# CC_SoC_Debugger_Ver1_02.net
KiCad netlist of a schematic drawn in Altium Designer
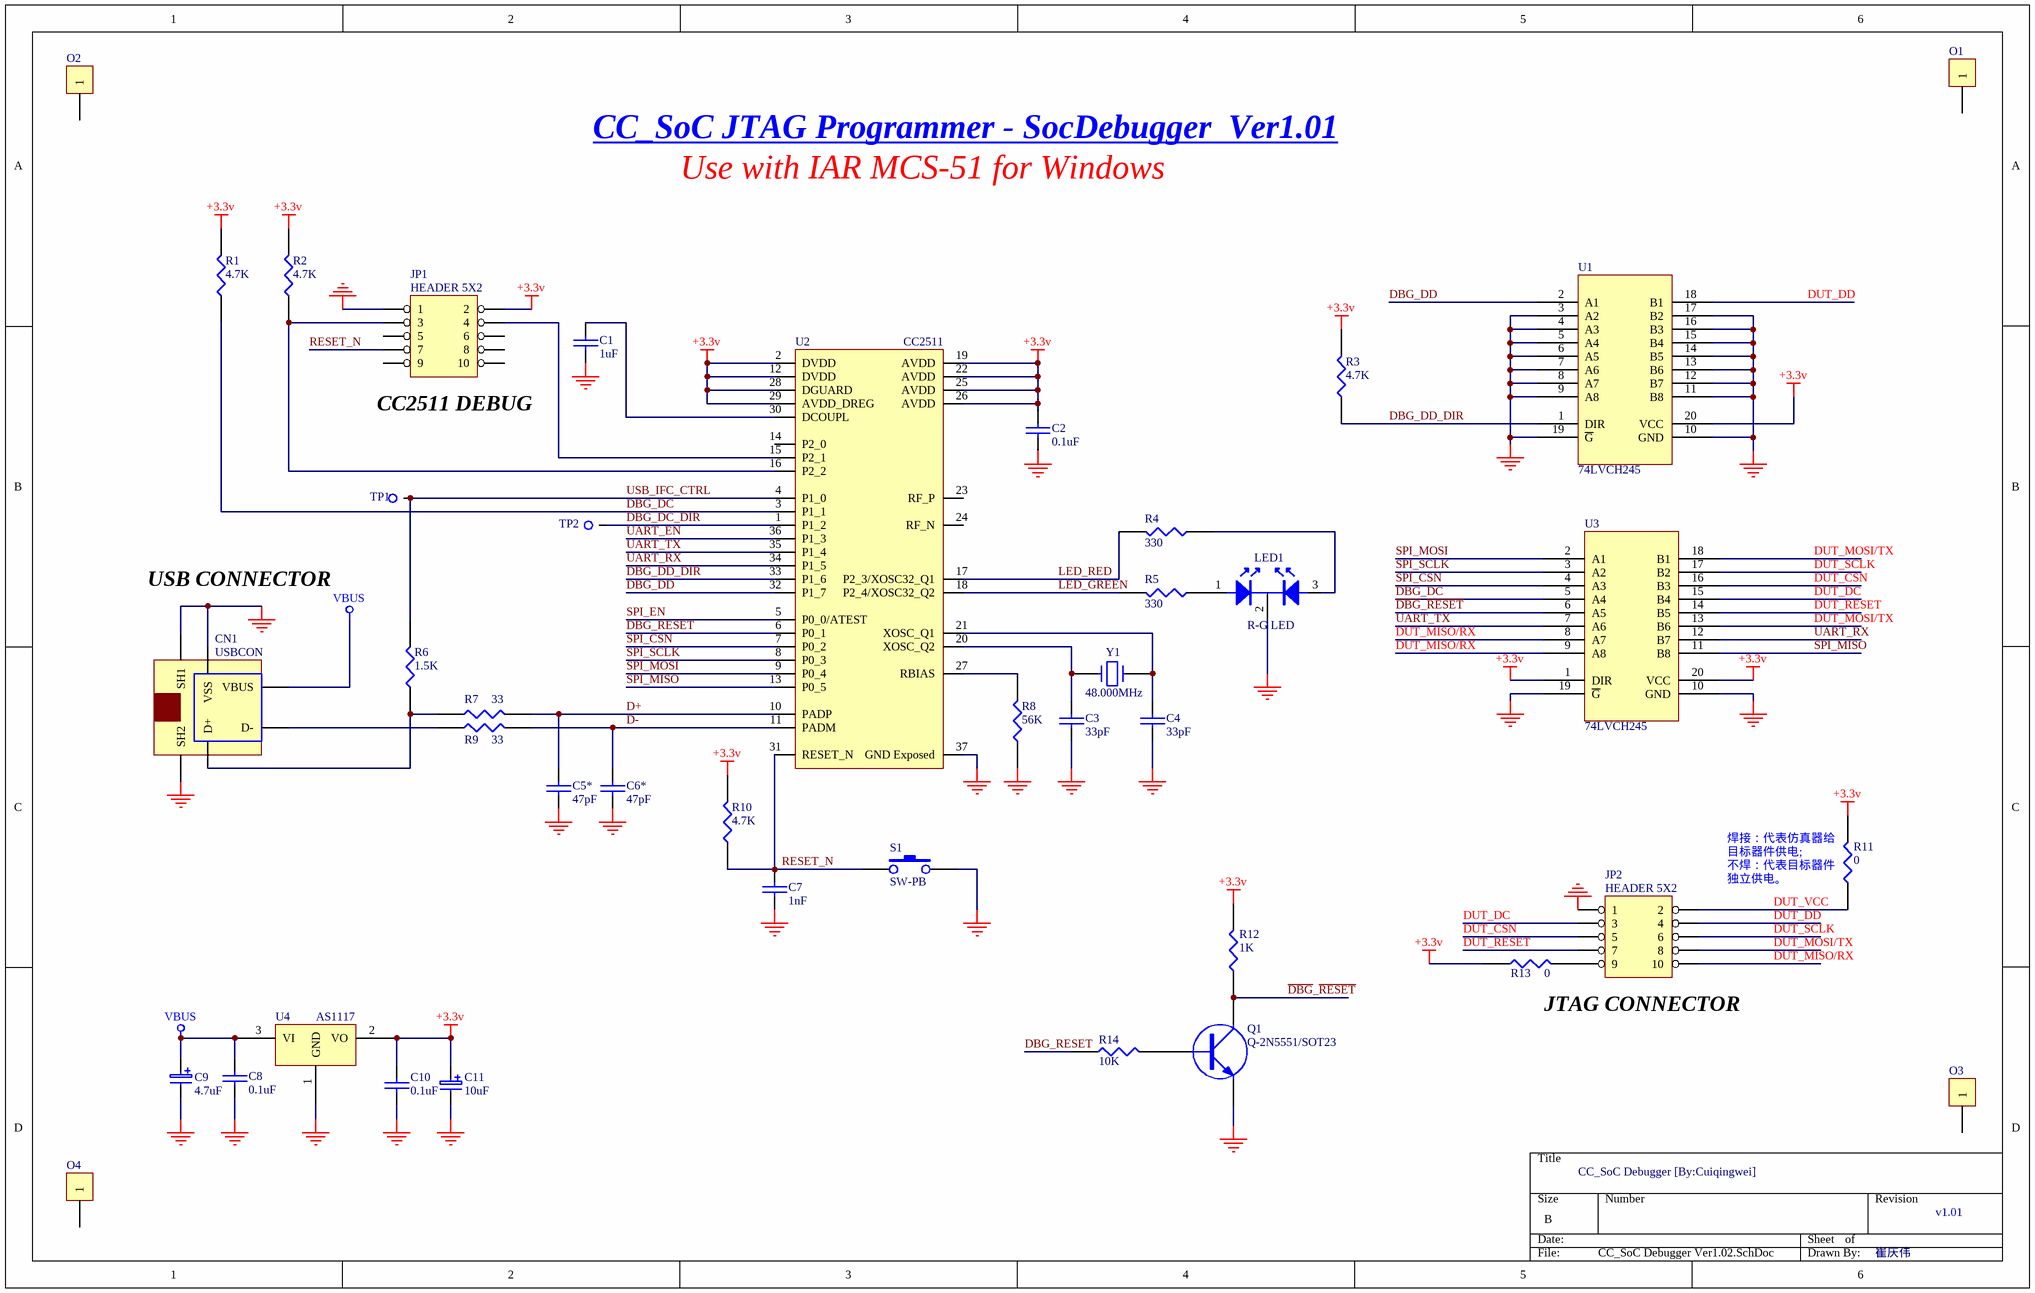
[diagram p0: CC_SoC Debugger Ver1.02.SchDoc]

(export (version "E")
  (design (tool "Eeschema 10.0.6"))
  (components
    (comp (ref "C1")
      (value "1uF")
      (footprint "0805")
      (description "Capacitor")
      (libsource (lib "*") (part "CAP"))
    )
    (comp (ref "C2")
      (value "0.1uF")
      (footprint "0805")
      (description "Capacitor")
      (libsource (lib "*") (part "CAP"))
    )
    (comp (ref "C3")
      (value "33pF")
      (footprint "0805")
      (description "Capacitor")
      (libsource (lib "*") (part "CAP"))
    )
    (comp (ref "C4")
      (value "33pF")
      (footprint "0805")
      (description "Capacitor")
      (libsource (lib "*") (part "CAP"))
    )
    (comp (ref "C5*")
      (value "47pF")
      (footprint "0805")
      (description "Capacitor")
      (libsource (lib "*") (part "CAP"))
    )
    (comp (ref "C6*")
      (value "47pF")
      (footprint "0805")
      (description "Capacitor")
      (libsource (lib "*") (part "CAP"))
    )
    (comp (ref "C7")
      (value "1nF")
      (footprint "0805")
      (description "Capacitor")
      (libsource (lib "*") (part "CAP"))
    )
    (comp (ref "C8")
      (value "0.1uF")
      (footprint "0805")
      (description "Capacitor")
      (libsource (lib "*") (part "CAP"))
    )
    (comp (ref "C9") (value "4.7uF") (footprint "1206") (libsource (lib "*") (part "C2")))
    (comp (ref "C10")
      (value "0.1uF")
      (footprint "0805")
      (description "Capacitor")
      (libsource (lib "*") (part "CAP"))
    )
    (comp (ref "C11") (value "10uF") (footprint "1206") (libsource (lib "*") (part "C2")))
    (comp (ref "CN1")
      (value "USBCON")
      (footprint "USB-B")
      (description "Connector")
      (libsource (lib "*") (part "USBCON"))
    )
    (comp (ref "JP1") (value "HEADER 5X2") (footprint "HDR5X2-LP") (libsource (lib "*") (part "HEADER 5X2")))
    (comp (ref "JP2") (value "HEADER 5X2") (footprint "FKV10LN") (libsource (lib "*") (part "HEADER 5X2")))
    (comp (ref "LED1")
      (value "R-G LED")
      (footprint "LED-05/KC/C")
      (description "312")
      (libsource (lib "routon_sch") (part "LED-05/KC/COMMON_K"))
    )
    (comp (ref "O1")
      (value "~")
      (footprint "HOLE3_1")
      (description "Connector")
      (libsource (lib "*") (part "CON1"))
    )
    (comp (ref "O2")
      (value "~")
      (footprint "HOLE3_1")
      (description "Connector")
      (libsource (lib "*") (part "CON1"))
    )
    (comp (ref "O3")
      (value "~")
      (footprint "HOLE3_1")
      (description "Connector")
      (libsource (lib "*") (part "CON1"))
    )
    (comp (ref "O4")
      (value "~")
      (footprint "HOLE3_1")
      (description "Connector")
      (libsource (lib "*") (part "CON1"))
    )
    (comp (ref "Q1")
      (value "Q-2N5551/SOT23")
      (footprint "sot23")
      (description "311000001")
      (libsource (lib "routon_sch") (part "Q-2N5551/SOT23"))
    )
    (comp (ref "R1") (value "4.7K") (footprint "0805") (libsource (lib "*") (part "RES1")))
    (comp (ref "R2") (value "4.7K") (footprint "0805") (libsource (lib "*") (part "RES1")))
    (comp (ref "R3") (value "4.7K") (footprint "0805") (libsource (lib "*") (part "RES1")))
    (comp (ref "R4") (value "330") (footprint "0805") (libsource (lib "*") (part "RES1")))
    (comp (ref "R5") (value "330") (footprint "0805") (libsource (lib "*") (part "RES1")))
    (comp (ref "R6") (value "1.5K") (footprint "0805") (libsource (lib "*") (part "RES1")))
    (comp (ref "R7") (value "33") (footprint "0805") (libsource (lib "*") (part "RES1")))
    (comp (ref "R8") (value "56K") (footprint "0805") (libsource (lib "*") (part "RES1")))
    (comp (ref "R9") (value "33") (footprint "0805") (libsource (lib "*") (part "RES1")))
    (comp (ref "R10") (value "4.7K") (footprint "0805") (libsource (lib "*") (part "RES1")))
    (comp (ref "R11") (value "0") (footprint "0805") (libsource (lib "*") (part "RES1")))
    (comp (ref "R12") (value "1K") (footprint "0805") (libsource (lib "*") (part "RES1")))
    (comp (ref "R13") (value "0") (footprint "0805") (libsource (lib "*") (part "RES1")))
    (comp (ref "R14") (value "10K") (footprint "0805") (libsource (lib "*") (part "RES1")))
    (comp (ref "S1") (value "SW-PB") (footprint "B3F-31XX") (libsource (lib "*") (part "SW-PB")))
    (comp (ref "TP1") (value "TP1") (footprint "TESTPOINT-PAD35") (libsource (lib "rf4ce_sch") (part "TP")))
    (comp (ref "TP2") (value "TP3") (footprint "TESTPOINT-PAD35") (libsource (lib "rf4ce_sch") (part "TP")))
    (comp (ref "U1")
      (value "74LVCH245")
      (footprint "SO20/1.27/9.652")
      (description "313")
      (libsource (lib "routon_sch") (part "74LVCH245"))
    )
    (comp (ref "U2") (value "CC2511") (footprint "CC2511") (libsource (lib "*") (part "CC2511")))
    (comp (ref "U3")
      (value "74LVCH245")
      (footprint "SO20/1.27/9.652")
      (description "313")
      (libsource (lib "routon_sch") (part "74LVCH245"))
    )
    (comp (ref "U4") (value "AS1117") (footprint "SOT-223") (libsource (lib "*") (part "AS1117")))
    (comp (ref "Y1")
      (value "48.000MHz")
      (footprint "XTAL-6X3.5")
      (libsource (lib "rf4ce_sch") (part "XTAL_SMD_4X2_5(4.0_X_2.5_MM)"))
    )
  )
  (nets
    (net (code "1") (name "+3.3v") (class "Default")
      (node (ref "C10") (pin "1") (pinfunction "1_1") (pintype "passive"))
      (node (ref "C11") (pin "1") (pinfunction "+_1") (pintype "passive"))
      (node (ref "C2") (pin "1") (pinfunction "1_1") (pintype "passive"))
      (node (ref "JP1") (pin "2") (pinfunction "2_2") (pintype "passive"))
      (node (ref "R1") (pin "2") (pinfunction "2_2") (pintype "passive"))
      (node (ref "R10") (pin "2") (pinfunction "2_2") (pintype "passive"))
      (node (ref "R11") (pin "2") (pinfunction "2_2") (pintype "passive"))
      (node (ref "R12") (pin "2") (pinfunction "2_2") (pintype "passive"))
      (node (ref "R13") (pin "1") (pinfunction "1_1") (pintype "passive"))
      (node (ref "R2") (pin "2") (pinfunction "2_2") (pintype "passive"))
      (node (ref "R3") (pin "2") (pinfunction "2_2") (pintype "passive"))
      (node (ref "U1") (pin "20") (pinfunction "VCC_20") (pintype "passive"))
      (node (ref "U2") (pin "12") (pinfunction "DVDD_12") (pintype "passive"))
      (node (ref "U2") (pin "19") (pinfunction "AVDD_19") (pintype "passive"))
      (node (ref "U2") (pin "2") (pinfunction "DVDD_2") (pintype "passive"))
      (node (ref "U2") (pin "22") (pinfunction "AVDD_22") (pintype "passive"))
      (node (ref "U2") (pin "25") (pinfunction "AVDD_25") (pintype "passive"))
      (node (ref "U2") (pin "26") (pinfunction "AVDD_26") (pintype "passive"))
      (node (ref "U2") (pin "28") (pinfunction "DGUARD_28") (pintype "passive"))
      (node (ref "U2") (pin "29") (pinfunction "AVDD_DREG_29") (pintype "passive"))
      (node (ref "U3") (pin "1") (pinfunction "DIR_1") (pintype "passive"))
      (node (ref "U3") (pin "20") (pinfunction "VCC_20") (pintype "passive"))
      (node (ref "U4") (pin "2") (pinfunction "VO_2") (pintype "passive"))
    )
    (net (code "2") (name "/D+") (class "Default")
      (node (ref "C5*") (pin "1") (pinfunction "1_1") (pintype "passive"))
      (node (ref "R7") (pin "2") (pinfunction "2_2") (pintype "passive"))
      (node (ref "U2") (pin "10") (pinfunction "PADP_10") (pintype "passive"))
    )
    (net (code "3") (name "/D-") (class "Default")
      (node (ref "C6*") (pin "1") (pinfunction "1_1") (pintype "passive"))
      (node (ref "R9") (pin "2") (pinfunction "2_2") (pintype "passive"))
      (node (ref "U2") (pin "11") (pinfunction "PADM_11") (pintype "passive"))
    )
    (net (code "4") (name "/DBG_DC") (class "Default")
      (node (ref "R1") (pin "1") (pinfunction "1_1") (pintype "passive"))
      (node (ref "U2") (pin "3") (pinfunction "P1_1_3") (pintype "passive"))
      (node (ref "U3") (pin "5") (pinfunction "A4_5") (pintype "passive"))
    )
    (net (code "5") (name "/DBG_DC_DIR") (class "Default")
      (node (ref "TP2") (pin "1") (pinfunction "1_1") (pintype "passive"))
      (node (ref "U2") (pin "1") (pinfunction "P1_2_1") (pintype "passive"))
    )
    (net (code "6") (name "/DBG_DD") (class "Default")
      (node (ref "U1") (pin "2") (pinfunction "A1_2") (pintype "passive"))
      (node (ref "U2") (pin "32") (pinfunction "P1_7_32") (pintype "passive"))
    )
    (net (code "7") (name "/DBG_DD_DIR") (class "Default")
      (node (ref "R3") (pin "1") (pinfunction "1_1") (pintype "passive"))
      (node (ref "U1") (pin "1") (pinfunction "DIR_1") (pintype "passive"))
      (node (ref "U2") (pin "33") (pinfunction "P1_6_33") (pintype "passive"))
    )
    (net (code "8") (name "/DBG_RESET") (class "Default")
      (node (ref "R14") (pin "1") (pinfunction "1_1") (pintype "passive"))
      (node (ref "U2") (pin "6") (pinfunction "P0_1_6") (pintype "passive"))
    )
    (net (code "9") (name "/DUT_CSN") (class "Default")
      (node (ref "JP2") (pin "5") (pinfunction "5_5") (pintype "passive"))
      (node (ref "U3") (pin "16") (pinfunction "B3_16") (pintype "passive"))
    )
    (net (code "10") (name "/DUT_DC") (class "Default")
      (node (ref "JP2") (pin "3") (pinfunction "3_3") (pintype "passive"))
      (node (ref "U3") (pin "15") (pinfunction "B4_15") (pintype "passive"))
    )
    (net (code "11") (name "/DUT_DD") (class "Default")
      (node (ref "JP2") (pin "4") (pinfunction "4_4") (pintype "passive"))
      (node (ref "U1") (pin "18") (pinfunction "B1_18") (pintype "passive"))
    )
    (net (code "12") (name "/DUT_MISO{slash}RX") (class "Default")
      (node (ref "JP2") (pin "10") (pinfunction "10_10") (pintype "passive"))
      (node (ref "U3") (pin "8") (pinfunction "A7_8") (pintype "passive"))
      (node (ref "U3") (pin "9") (pinfunction "A8_9") (pintype "passive"))
    )
    (net (code "13") (name "/DUT_MOSI{slash}TX") (class "Default")
      (node (ref "JP2") (pin "8") (pinfunction "8_8") (pintype "passive"))
      (node (ref "U3") (pin "13") (pinfunction "B6_13") (pintype "passive"))
      (node (ref "U3") (pin "18") (pinfunction "B1_18") (pintype "passive"))
    )
    (net (code "14") (name "/DUT_RESET") (class "Default")
      (node (ref "JP2") (pin "7") (pinfunction "7_7") (pintype "passive"))
      (node (ref "U3") (pin "14") (pinfunction "B5_14") (pintype "passive"))
    )
    (net (code "15") (name "/DUT_SCLK") (class "Default")
      (node (ref "JP2") (pin "6") (pinfunction "6_6") (pintype "passive"))
      (node (ref "U3") (pin "17") (pinfunction "B2_17") (pintype "passive"))
    )
    (net (code "16") (name "/DUT_VCC") (class "Default")
      (node (ref "JP2") (pin "2") (pinfunction "2_2") (pintype "passive"))
      (node (ref "R11") (pin "1") (pinfunction "1_1") (pintype "passive"))
    )
    (net (code "17") (name "/LED_GREEN") (class "Default")
      (node (ref "R5") (pin "2") (pinfunction "2_2") (pintype "passive"))
      (node (ref "U2") (pin "18") (pinfunction "P2_4/XOSC32_Q2_18") (pintype "passive"))
    )
    (net (code "18") (name "/LED_RED") (class "Default")
      (node (ref "R4") (pin "2") (pinfunction "2_2") (pintype "passive"))
      (node (ref "U2") (pin "17") (pinfunction "P2_3/XOSC32_Q1_17") (pintype "passive"))
    )
    (net (code "19") (name "/RESET_N") (class "Default")
      (node (ref "C7") (pin "1") (pinfunction "1_1") (pintype "passive"))
      (node (ref "JP1") (pin "7") (pinfunction "7_7") (pintype "passive"))
      (node (ref "R10") (pin "1") (pinfunction "1_1") (pintype "passive"))
      (node (ref "S1") (pin "1") (pinfunction "1_1") (pintype "passive"))
      (node (ref "U2") (pin "31") (pinfunction "RESET_N_31") (pintype "passive"))
    )
    (net (code "20") (name "/SPI_CSN") (class "Default")
      (node (ref "U2") (pin "7") (pinfunction "P0_2_7") (pintype "passive"))
      (node (ref "U3") (pin "4") (pinfunction "A3_4") (pintype "passive"))
    )
    (net (code "21") (name "/SPI_EN") (class "Default")
      (node (ref "U2") (pin "5") (pinfunction "P0_0/ATEST_5") (pintype "passive"))
    )
    (net (code "22") (name "/SPI_MISO") (class "Default")
      (node (ref "U2") (pin "13") (pinfunction "P0_5_13") (pintype "passive"))
      (node (ref "U3") (pin "11") (pinfunction "B8_11") (pintype "passive"))
    )
    (net (code "23") (name "/SPI_MOSI") (class "Default")
      (node (ref "U2") (pin "9") (pinfunction "P0_4_9") (pintype "passive"))
      (node (ref "U3") (pin "2") (pinfunction "A1_2") (pintype "passive"))
    )
    (net (code "24") (name "/SPI_SCLK") (class "Default")
      (node (ref "U2") (pin "8") (pinfunction "P0_3_8") (pintype "passive"))
      (node (ref "U3") (pin "3") (pinfunction "A2_3") (pintype "passive"))
    )
    (net (code "25") (name "/UART_EN") (class "Default")
      (node (ref "U2") (pin "36") (pinfunction "P1_3_36") (pintype "passive"))
    )
    (net (code "26") (name "/UART_RX") (class "Default")
      (node (ref "U2") (pin "34") (pinfunction "P1_5_34") (pintype "passive"))
      (node (ref "U3") (pin "12") (pinfunction "B7_12") (pintype "passive"))
    )
    (net (code "27") (name "/UART_TX") (class "Default")
      (node (ref "U2") (pin "35") (pinfunction "P1_4_35") (pintype "passive"))
      (node (ref "U3") (pin "7") (pinfunction "A6_7") (pintype "passive"))
    )
    (net (code "28") (name "/USB_IFC_CTRL") (class "Default")
      (node (ref "R6") (pin "2") (pinfunction "2_2") (pintype "passive"))
      (node (ref "TP1") (pin "1") (pinfunction "1_1") (pintype "passive"))
      (node (ref "U2") (pin "4") (pinfunction "P1_0_4") (pintype "passive"))
    )
    (net (code "30") (name "/~{DBG}_~{RESET}") (class "Default")
      (node (ref "Q1") (pin "3") (pinfunction "C_3") (pintype "passive"))
      (node (ref "R12") (pin "1") (pinfunction "1_1") (pintype "passive"))
      (node (ref "U3") (pin "6") (pinfunction "A5_6") (pintype "passive"))
    )
    (net (code "31") (name "GND") (class "Default")
      (node (ref "C1") (pin "2") (pinfunction "2_2") (pintype "passive"))
      (node (ref "C10") (pin "2") (pinfunction "2_2") (pintype "passive"))
      (node (ref "C11") (pin "2") (pinfunction "-_2") (pintype "passive"))
      (node (ref "C2") (pin "2") (pinfunction "2_2") (pintype "passive"))
      (node (ref "C3") (pin "2") (pinfunction "2_2") (pintype "passive"))
      (node (ref "C4") (pin "2") (pinfunction "2_2") (pintype "passive"))
      (node (ref "C5*") (pin "2") (pinfunction "2_2") (pintype "passive"))
      (node (ref "C6*") (pin "2") (pinfunction "2_2") (pintype "passive"))
      (node (ref "C7") (pin "2") (pinfunction "2_2") (pintype "passive"))
      (node (ref "C8") (pin "2") (pinfunction "2_2") (pintype "passive"))
      (node (ref "C9") (pin "2") (pinfunction "-_2") (pintype "passive"))
      (node (ref "CN1") (pin "SH1") (pinfunction "SH1_SH1") (pintype "passive"))
      (node (ref "CN1") (pin "SH2") (pinfunction "SH2_SH2") (pintype "passive"))
      (node (ref "CN1") (pin "VSS") (pinfunction "VSS_VSS") (pintype "passive"))
      (node (ref "JP1") (pin "1") (pinfunction "1_1") (pintype "passive"))
      (node (ref "JP2") (pin "1") (pinfunction "1_1") (pintype "passive"))
      (node (ref "LED1") (pin "2") (pinfunction "K_2") (pintype "passive"))
      (node (ref "Q1") (pin "2") (pinfunction "E_2") (pintype "passive"))
      (node (ref "R8") (pin "1") (pinfunction "1_1") (pintype "passive"))
      (node (ref "S1") (pin "2") (pinfunction "2_2") (pintype "passive"))
      (node (ref "U1") (pin "10") (pinfunction "GND_10") (pintype "passive"))
      (node (ref "U1") (pin "11") (pinfunction "B8_11") (pintype "passive"))
      (node (ref "U1") (pin "12") (pinfunction "B7_12") (pintype "passive"))
      (node (ref "U1") (pin "13") (pinfunction "B6_13") (pintype "passive"))
      (node (ref "U1") (pin "14") (pinfunction "B5_14") (pintype "passive"))
      (node (ref "U1") (pin "15") (pinfunction "B4_15") (pintype "passive"))
      (node (ref "U1") (pin "16") (pinfunction "B3_16") (pintype "passive"))
      (node (ref "U1") (pin "17") (pinfunction "B2_17") (pintype "passive"))
      (node (ref "U1") (pin "19") (pinfunction "~{G}_19") (pintype "passive"))
      (node (ref "U1") (pin "3") (pinfunction "A2_3") (pintype "passive"))
      (node (ref "U1") (pin "4") (pinfunction "A3_4") (pintype "passive"))
      (node (ref "U1") (pin "5") (pinfunction "A4_5") (pintype "passive"))
      (node (ref "U1") (pin "6") (pinfunction "A5_6") (pintype "passive"))
      (node (ref "U1") (pin "7") (pinfunction "A6_7") (pintype "passive"))
      (node (ref "U1") (pin "8") (pinfunction "A7_8") (pintype "passive"))
      (node (ref "U1") (pin "9") (pinfunction "A8_9") (pintype "passive"))
      (node (ref "U2") (pin "37") (pinfunction "GND_Exposed_37") (pintype "passive"))
      (node (ref "U3") (pin "10") (pinfunction "GND_10") (pintype "passive"))
      (node (ref "U3") (pin "19") (pinfunction "~{G}_19") (pintype "passive"))
      (node (ref "U4") (pin "1") (pinfunction "GND_1") (pintype "passive"))
    )
    (net (code "32") (name "Net-(CN1-PadD+)") (class "Default")
      (node (ref "CN1") (pin "D+") (pinfunction "D+_D+") (pintype "passive"))
      (node (ref "R6") (pin "1") (pinfunction "1_1") (pintype "passive"))
      (node (ref "R7") (pin "1") (pinfunction "1_1") (pintype "passive"))
    )
    (net (code "33") (name "Net-(CN1-PadD-)") (class "Default")
      (node (ref "CN1") (pin "D-") (pinfunction "D-_D-") (pintype "passive"))
      (node (ref "R9") (pin "1") (pinfunction "1_1") (pintype "passive"))
    )
    (net (code "34") (name "Net-(JP2-Pad9)") (class "Default")
      (node (ref "JP2") (pin "9") (pinfunction "9_9") (pintype "passive"))
      (node (ref "R13") (pin "2") (pinfunction "2_2") (pintype "passive"))
    )
    (net (code "35") (name "Net-(LED1-A-Pad1)") (class "Default")
      (node (ref "LED1") (pin "1") (pinfunction "A_1") (pintype "passive"))
      (node (ref "R5") (pin "1") (pinfunction "1_1") (pintype "passive"))
    )
    (net (code "36") (name "Net-(LED1-A-Pad3)") (class "Default")
      (node (ref "LED1") (pin "3") (pinfunction "A_3") (pintype "passive"))
      (node (ref "R4") (pin "1") (pinfunction "1_1") (pintype "passive"))
    )
    (net (code "37") (name "Net-(Q1-B)") (class "Default")
      (node (ref "Q1") (pin "1") (pinfunction "B_1") (pintype "passive"))
      (node (ref "R14") (pin "2") (pinfunction "2_2") (pintype "passive"))
    )
    (net (code "38") (name "Net-(U2-DCOUPL)") (class "Default")
      (node (ref "C1") (pin "1") (pinfunction "1_1") (pintype "passive"))
      (node (ref "U2") (pin "30") (pinfunction "DCOUPL_30") (pintype "passive"))
    )
    (net (code "39") (name "Net-(U2-P2_1)") (class "Default")
      (node (ref "JP1") (pin "4") (pinfunction "4_4") (pintype "passive"))
      (node (ref "U2") (pin "15") (pinfunction "P2_1_15") (pintype "passive"))
    )
    (net (code "40") (name "Net-(U2-P2_2)") (class "Default")
      (node (ref "JP1") (pin "3") (pinfunction "3_3") (pintype "passive"))
      (node (ref "R2") (pin "1") (pinfunction "1_1") (pintype "passive"))
      (node (ref "U2") (pin "16") (pinfunction "P2_2_16") (pintype "passive"))
    )
    (net (code "41") (name "Net-(U2-RBIAS)") (class "Default")
      (node (ref "R8") (pin "2") (pinfunction "2_2") (pintype "passive"))
      (node (ref "U2") (pin "27") (pinfunction "RBIAS_27") (pintype "passive"))
    )
    (net (code "42") (name "Net-(U2-XOSC_Q1)") (class "Default")
      (node (ref "C4") (pin "1") (pinfunction "1_1") (pintype "passive"))
      (node (ref "U2") (pin "21") (pinfunction "XOSC_Q1_21") (pintype "passive"))
      (node (ref "Y1") (pin "3") (pinfunction "3_3") (pintype "passive"))
    )
    (net (code "43") (name "Net-(U2-XOSC_Q2)") (class "Default")
      (node (ref "C3") (pin "1") (pinfunction "1_1") (pintype "passive"))
      (node (ref "U2") (pin "20") (pinfunction "XOSC_Q2_20") (pintype "passive"))
      (node (ref "Y1") (pin "1") (pinfunction "1_1") (pintype "passive"))
    )
    (net (code "44") (name "VBUS") (class "Default")
      (node (ref "C8") (pin "1") (pinfunction "1_1") (pintype "passive"))
      (node (ref "C9") (pin "1") (pinfunction "+_1") (pintype "passive"))
      (node (ref "CN1") (pin "VBUS") (pinfunction "VBUS_VBUS") (pintype "passive"))
      (node (ref "U4") (pin "3") (pinfunction "VI_3") (pintype "passive"))
    )
    (net (code "45") (name "unconnected-(JP1-Pad5)") (class "Default")
      (node (ref "JP1") (pin "5") (pinfunction "5_5") (pintype "passive"))
    )
    (net (code "46") (name "unconnected-(JP1-Pad6)") (class "Default")
      (node (ref "JP1") (pin "6") (pinfunction "6_6") (pintype "passive"))
    )
    (net (code "47") (name "unconnected-(JP1-Pad8)") (class "Default")
      (node (ref "JP1") (pin "8") (pinfunction "8_8") (pintype "passive"))
    )
    (net (code "48") (name "unconnected-(JP1-Pad9)") (class "Default")
      (node (ref "JP1") (pin "9") (pinfunction "9_9") (pintype "passive"))
    )
    (net (code "49") (name "unconnected-(JP1-Pad10)") (class "Default")
      (node (ref "JP1") (pin "10") (pinfunction "10_10") (pintype "passive"))
    )
    (net (code "50") (name "unconnected-(O1-Pad1)") (class "Default")
      (node (ref "O1") (pin "1") (pinfunction "1_1") (pintype "passive"))
    )
    (net (code "51") (name "unconnected-(O2-Pad1)") (class "Default")
      (node (ref "O2") (pin "1") (pinfunction "1_1") (pintype "passive"))
    )
    (net (code "52") (name "unconnected-(O3-Pad1)") (class "Default")
      (node (ref "O3") (pin "1") (pinfunction "1_1") (pintype "passive"))
    )
    (net (code "53") (name "unconnected-(O4-Pad1)") (class "Default")
      (node (ref "O4") (pin "1") (pinfunction "1_1") (pintype "passive"))
    )
    (net (code "54") (name "unconnected-(U2-P2_0-Pad14)") (class "Default")
      (node (ref "U2") (pin "14") (pinfunction "P2_0_14") (pintype "passive"))
    )
    (net (code "55") (name "unconnected-(U2-RF_N-Pad24)") (class "Default")
      (node (ref "U2") (pin "24") (pinfunction "RF_N_24") (pintype "passive"))
    )
    (net (code "56") (name "unconnected-(U2-RF_P-Pad23)") (class "Default")
      (node (ref "U2") (pin "23") (pinfunction "RF_P_23") (pintype "passive"))
    )
  )
)
